# Power-SMPS.net
KiCad netlist of a schematic drawn in Altium Designer
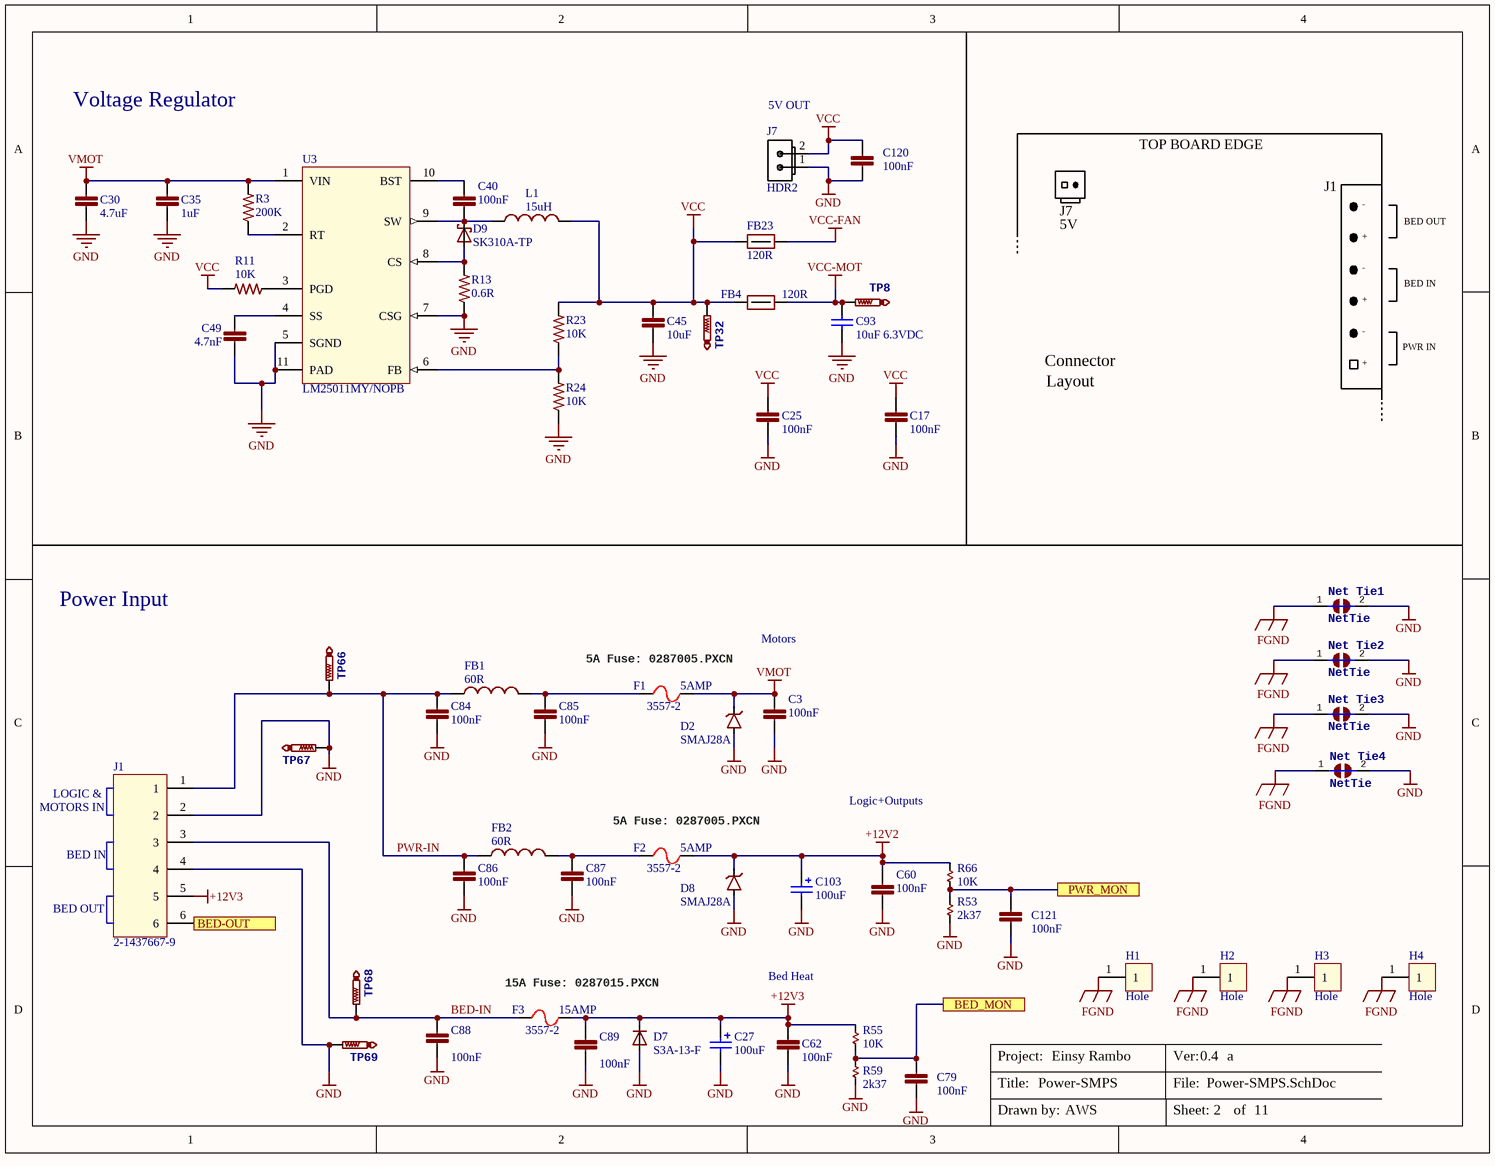
[diagram p0: Power-SMPS.SchDoc]

(export (version "E")
  (design (tool "Eeschema 10.0.6"))
  (components
    (comp (ref "C3")
      (value "100nF")
      (footprint "C0603")
      (description "CAP CER 0603 100nF 50V 10% X7R")
      (fields (field (name "MANUFACTURER") "Kemet") (field (name "TOLERANCE") "+/- 10%"))
      (libsource (lib "3Delight") (part "C0603C104K5RACTU"))
    )
    (comp (ref "C17")
      (value "100nF")
      (footprint "C0402")
      (description "CAP CER 0402 100nF 16V 10% X7R")
      (fields (field (name "MANUFACTURER") "Murata") (field (name "TOLERANCE") "+/- 10%"))
      (libsource (lib "") (part "GRM155R71C104KA88D_2"))
    )
    (comp (ref "C25")
      (value "100nF")
      (footprint "C0603")
      (description "CAP CER 0603 100nF 50V 10% X7R")
      (fields (field (name "MANUFACTURER") "Kemet") (field (name "TOLERANCE") "+/- 10%"))
      (libsource (lib "3Delight") (part "C0603C104K5RACTU"))
    )
    (comp (ref "C27")
      (value "100uF")
      (footprint "CAP-ELEC-063063077")
      (description "CAP ALUM 100UF 35V 20% SMD")
      (fields (field (name "MANUFACTURER") "Nichicon") (field (name "TOLERANCE") "+/- 20%"))
      (libsource (lib "3Delight") (part "UWT1V101MCL1GS"))
    )
    (comp (ref "C30")
      (value "4.7uF")
      (footprint "C1206")
      (description "CAP CER 1206 4.7uF 50V 10% X5R")
      (fields (field (name "MANUFACTURER") "Kemet") (field (name "TOLERANCE") "+/- 10%"))
      (libsource (lib "3Delight") (part "C1206C475K5PACTU"))
    )
    (comp (ref "C35")
      (value "1uF")
      (footprint "C0805")
      (description "CAP CER 0805 1uF 50V 10% X7R")
      (fields (field (name "MANUFACTURER") "Murata") (field (name "TOLERANCE") "+/- 10%"))
      (libsource (lib "3Delight") (part "GRM21BR71H105KA12L"))
    )
    (comp (ref "C40")
      (value "100nF")
      (footprint "C0603")
      (description "CAP CER 0603 100nF 50V 10% X7R")
      (fields (field (name "MANUFACTURER") "Kemet") (field (name "TOLERANCE") "+/- 10%"))
      (libsource (lib "3Delight") (part "C0603C104K5RACTU"))
    )
    (comp (ref "C45")
      (value "10uF")
      (footprint "C0805")
      (description "CAP CER 0805 10uF 10V 10% X5R")
      (fields (field (name "MANUFACTURER") "Kemet") (field (name "TOLERANCE") "+/- 10%"))
      (libsource (lib "3Delight") (part "C0805C106K8PACTU"))
    )
    (comp (ref "C49")
      (value "4.7nF")
      (footprint "C0402")
      (description "CAP CER 0402 4.7nF 25V 10% X7R")
      (fields (field (name "MANUFACTURER") "YAGEO") (field (name "TOLERANCE") "+/- 10%"))
      (libsource (lib "3Delight") (part "CC0402KRX7R8BB472"))
    )
    (comp (ref "C60")
      (value "100nF")
      (footprint "C0603")
      (description "CAP CER 0603 100nF 50V 10% X7R")
      (fields (field (name "MANUFACTURER") "Kemet") (field (name "TOLERANCE") "+/- 10%"))
      (libsource (lib "3Delight") (part "C0603C104K5RACTU"))
    )
    (comp (ref "C62")
      (value "100nF")
      (footprint "C0603")
      (description "CAP CER 0603 100nF 50V 10% X7R")
      (fields (field (name "MANUFACTURER") "Kemet") (field (name "TOLERANCE") "+/- 10%"))
      (libsource (lib "3Delight") (part "C0603C104K5RACTU"))
    )
    (comp (ref "C79")
      (value "100nF")
      (footprint "C0402")
      (description "CAP CER 0402 100nF 16V 10% X7R")
      (fields (field (name "MANUFACTURER") "Murata") (field (name "TOLERANCE") "+/- 10%"))
      (libsource (lib "") (part "GRM155R71C104KA88D_1"))
    )
    (comp (ref "C84")
      (value "100nF")
      (footprint "C0603")
      (description "CAP CER 0603 100nF 50V 10% X7R")
      (fields (field (name "MANUFACTURER") "Kemet") (field (name "TOLERANCE") "+/- 10%"))
      (libsource (lib "3Delight") (part "C0603C104K5RACTU"))
    )
    (comp (ref "C85")
      (value "100nF")
      (footprint "C0603")
      (description "CAP CER 0603 100nF 50V 10% X7R")
      (fields (field (name "MANUFACTURER") "Kemet") (field (name "TOLERANCE") "+/- 10%"))
      (libsource (lib "3Delight") (part "C0603C104K5RACTU"))
    )
    (comp (ref "C86")
      (value "100nF")
      (footprint "C0603")
      (description "CAP CER 0603 100nF 50V 10% X7R")
      (fields (field (name "MANUFACTURER") "Kemet") (field (name "TOLERANCE") "+/- 10%"))
      (libsource (lib "3Delight") (part "C0603C104K5RACTU"))
    )
    (comp (ref "C87")
      (value "100nF")
      (footprint "C0603")
      (description "CAP CER 0603 100nF 50V 10% X7R")
      (fields (field (name "MANUFACTURER") "Kemet") (field (name "TOLERANCE") "+/- 10%"))
      (libsource (lib "3Delight") (part "C0603C104K5RACTU"))
    )
    (comp (ref "C88")
      (value "100nF")
      (footprint "C0603")
      (description "CAP CER 0603 100nF 50V 10% X7R")
      (fields (field (name "MANUFACTURER") "Kemet") (field (name "TOLERANCE") "+/- 10%"))
      (libsource (lib "3Delight") (part "C0603C104K5RACTU"))
    )
    (comp (ref "C89")
      (value "100nF")
      (footprint "C0603")
      (description "CAP CER 0603 100nF 50V 10% X7R")
      (fields (field (name "MANUFACTURER") "Kemet") (field (name "TOLERANCE") "+/- 10%"))
      (libsource (lib "3Delight") (part "C0603C104K5RACTU"))
    )
    (comp (ref "C93")
      (value "10uF 6.3VDC")
      (footprint "C0603")
      (description "CAP CER 10UF 6.3V 10% JB 0603")
      (fields (field (name "TOLERANCE") "+/- 10%") (field (name "MANUFACTURER") "TDK"))
      (libsource (lib "Tigershark3D") (part "C1608JB0J106K080AB"))
    )
    (comp (ref "C103")
      (value "100uF")
      (footprint "CAP-ELEC-063063077")
      (description "CAP ALUM 100UF 35V 20% SMD")
      (fields (field (name "MANUFACTURER") "Nichicon") (field (name "TOLERANCE") "+/- 20%"))
      (libsource (lib "3Delight") (part "UWT1V101MCL1GS"))
    )
    (comp (ref "C120")
      (value "100nF")
      (footprint "C0402")
      (description "CAP CER 0402 100nF 16V 10% X7R")
      (fields (field (name "MANUFACTURER") "Murata") (field (name "TOLERANCE") "+/- 10%"))
      (libsource (lib "3Delight") (part "GRM155R71C104KA88D"))
    )
    (comp (ref "C121")
      (value "100nF")
      (footprint "C0402")
      (description "CAP CER 0402 100nF 16V 10% X7R")
      (fields (field (name "MANUFACTURER") "Murata") (field (name "TOLERANCE") "+/- 10%"))
      (libsource (lib "") (part "GRM155R71C104KA88D_1"))
    )
    (comp (ref "D2")
      (value "SMAJ28A")
      (footprint "SMA-SM")
      (description "TVS DIODE 28VWM 45.4VC SMA")
      (fields (field (name "MANUFACTURER") "Diodes Inc") (field (name "TOLERANCE") "NA"))
      (libsource (lib "Diodes") (part "SMAJ28A"))
    )
    (comp (ref "D7")
      (value "S3A-13-F")
      (footprint "DO-214AB")
      (description "DIODE DO-214AB")
      (fields (field (name "MANUFACTURER") "Diodes Incorporated") (field (name "TOLERANCE") "NA"))
      (libsource (lib "3Delight") (part "S3A-13-F"))
    )
    (comp (ref "D8")
      (value "SMAJ28A")
      (footprint "SMA-SM")
      (description "TVS DIODE 28VWM 45.4VC SMA")
      (fields (field (name "MANUFACTURER") "Diodes Inc") (field (name "TOLERANCE") "NA"))
      (libsource (lib "Diodes") (part "SMAJ28A"))
    )
    (comp (ref "D9")
      (value "SK310A-TP")
      (footprint "SMA-SM")
      (description "DIODE Schottky 3A SMA")
      (fields (field (name "MANUFACTURER") "MCC") (field (name "PART") "SK310A"))
      (libsource (lib "3Delight") (part "SK310A"))
    )
    (comp (ref "F1")
      (value "3557-2")
      (footprint "3557")
      (description "FUSE PTH ATO")
      (fields (field (name "MANUFACTURER") "Keystone") (field (name "PART") "Fuse"))
      (libsource (lib "3Delight") (part "3557-2"))
    )
    (comp (ref "F2")
      (value "3557-2")
      (footprint "3557")
      (description "FUSE PTH ATO")
      (fields (field (name "MANUFACTURER") "Keystone") (field (name "PART") "Fuse"))
      (libsource (lib "3Delight") (part "3557-2"))
    )
    (comp (ref "F3")
      (value "3557-2")
      (footprint "3557")
      (description "FUSE PTH ATO")
      (fields (field (name "MANUFACTURER") "Keystone") (field (name "PART") "Fuse"))
      (libsource (lib "3Delight") (part "3557-2"))
    )
    (comp (ref "FB1")
      (value "60R")
      (footprint "3Delight:L1806")
      (description "FERRITE BEAD 1806 60ohm")
      (fields (field (name "MANUFACTURER") "Murata") (field (name "PART") "60Rf"))
      (libsource (lib "3Delight") (part "BLM41PG600SN1L"))
    )
    (comp (ref "FB2")
      (value "60R")
      (footprint "3Delight:L1806")
      (description "FERRITE BEAD 1806 60ohm")
      (fields (field (name "MANUFACTURER") "Murata") (field (name "PART") "60Rf"))
      (libsource (lib "3Delight") (part "BLM41PG600SN1L"))
    )
    (comp (ref "FB4")
      (value "120R")
      (footprint "FB0603")
      (description "FERRITE BEAD 120 OHM 0603 1LN")
      (fields (field (name "MANUFACTURER") "Samsung") (field (name "PART") "FERRITE 120R 3A 0603"))
      (libsource (lib "3Delight") (part "FERRITE 220R 2.5A 0603"))
    )
    (comp (ref "FB23")
      (value "120R")
      (footprint "FB0603")
      (description "FERRITE BEAD 120 OHM 0603 1LN")
      (fields (field (name "MANUFACTURER") "Samsung") (field (name "PART") "FERRITE 120R 3A 0603"))
      (libsource (lib "Inductors") (part "FERRITE 120R 3A 0603"))
    )
    (comp (ref "H1")
      (value "Hole")
      (footprint "Wave_hole_3x7-singleSided")
      (libsource (lib "3Delight") (part "Hole"))
    )
    (comp (ref "H2")
      (value "Hole")
      (footprint "Wave_hole_3x7-singleSided")
      (libsource (lib "3Delight") (part "Hole"))
    )
    (comp (ref "H3")
      (value "Hole")
      (footprint "Wave_hole_3x7-singleSided")
      (libsource (lib "3Delight") (part "Hole"))
    )
    (comp (ref "H4")
      (value "Hole")
      (footprint "Wave_hole_3x7-singleSided")
      (libsource (lib "3Delight") (part "Hole"))
    )
    (comp (ref "J1")
      (value "2-1437667-9")
      (footprint "CON-Barrier-6-8.26mm")
      (description "CONN BARRIER STRIP 6CIRC 0.325\"")
      (fields (field (name "MANUFACTURER") "TE") (field (name "PART") "6POS"))
      (libsource (lib "3Delight") (part "2-1437667-9"))
    )
    (comp (ref "J7")
      (value "HDR2")
      (footprint "70543-02 PIN-IN-PASTE")
      (description "Connector 2pos")
      (fields (field (name "MANUFACTURER") "Molex") (field (name "PART") "2 Pin Conn"))
      (libsource (lib "Connectors") (part "CONN 2PIN VERT 0.1{dblquote} SHRD LOCKING PIN-IN-PASTE"))
    )
    (comp (ref "L1")
      (value "15uH")
      (footprint "XAL50xx_VLS6045")
      (description "FIXED IND 15UH 2.5A 98 MOHM SMD")
      (fields (field (name "MANUFACTURER") "TDK") (field (name "TOLERANCE") "+/- 20%"))
      (libsource (lib "3Delight") (part "IND 15uH 2.5A 0.075R"))
    )
    (comp (ref "Net Tie1")
      (value "NetTie")
      (footprint "Net Tie")
      (description "Net Tie")
      (fields (field (name "PUBLISHER") "UltiMachine"))
      (libsource (lib "3Delight") (part "NetTie"))
    )
    (comp (ref "Net Tie2")
      (value "NetTie")
      (footprint "Net Tie")
      (description "Net Tie")
      (fields (field (name "PUBLISHER") "UltiMachine"))
      (libsource (lib "3Delight") (part "NetTie"))
    )
    (comp (ref "Net Tie3")
      (value "NetTie")
      (footprint "Net Tie")
      (description "Net Tie")
      (fields (field (name "PUBLISHER") "UltiMachine"))
      (libsource (lib "3Delight") (part "NetTie"))
    )
    (comp (ref "Net Tie4")
      (value "NetTie")
      (footprint "Net Tie")
      (description "Net Tie")
      (fields (field (name "PUBLISHER") "UltiMachine"))
      (libsource (lib "3Delight") (part "NetTie"))
    )
    (comp (ref "R3")
      (value "200K")
      (footprint "R0402")
      (description "RES 0402 200K")
      (fields (field (name "MANUFACTURER") "Vishay Dale") (field (name "TOLERANCE") "+/- 1%"))
      (libsource (lib "3Delight") (part "CRCW0402200KFKED"))
    )
    (comp (ref "R11")
      (value "10K")
      (footprint "R0402")
      (description "RES SMD 10K OHM 1% 1/16W 0402")
      (fields (field (name "MANUFACTURER") "Yageo") (field (name "PART") "10k 1% 0402"))
      (libsource (lib "3Delight") (part "RC0402FR-0710KP"))
    )
    (comp (ref "R13")
      (value "0.6R")
      (footprint "2512R-0.55")
      (description "RES 0.06 OHM 1W 1% 2512 SMD")
      (fields (field (name "MANUFACTURER") "Yageo") (field (name "TOLERANCE") "1%"))
      (libsource (lib "3Delight") (part "RL2512FK-070R06L"))
    )
    (comp (ref "R23")
      (value "10K")
      (footprint "R0402")
      (description "RES SMD 10K OHM 1% 1/16W 0402")
      (fields (field (name "MANUFACTURER") "Yageo") (field (name "PART") "10k 1% 0402"))
      (libsource (lib "3Delight") (part "RC0402FR-0710KP"))
    )
    (comp (ref "R24")
      (value "10K")
      (footprint "R0402")
      (description "RES SMD 10K OHM 1% 1/16W 0402")
      (fields (field (name "MANUFACTURER") "Yageo") (field (name "PART") "10k 1% 0402"))
      (libsource (lib "3Delight") (part "RC0402FR-0710KP"))
    )
    (comp (ref "R53")
      (value "2k37")
      (footprint "R0402")
      (description "RES SMD 2.37K OHM 1% 1/16W 0402")
      (fields (field (name "MANUFACTURER") "Yageo") (field (name "PART") "2.37k"))
      (libsource (lib "3Delight") (part "RC0402FR-072K37L"))
    )
    (comp (ref "R55")
      (value "10K")
      (footprint "R0402")
      (description "RES SMD 10K OHM 1% 1/16W 0402")
      (fields (field (name "MANUFACTURER") "Yageo") (field (name "PART") "10k 1% 0402"))
      (libsource (lib "Resistors") (part "10k 1% 0402"))
    )
    (comp (ref "R59")
      (value "2k37")
      (footprint "R0402")
      (description "RES SMD 2.37K OHM 1% 1/16W 0402")
      (fields (field (name "MANUFACTURER") "Yageo") (field (name "PART") "2.37k"))
      (libsource (lib "3Delight") (part "RC0402FR-072K37L"))
    )
    (comp (ref "R66")
      (value "10K")
      (footprint "R0402")
      (description "RES SMD 10K OHM 1% 1/16W 0402")
      (fields (field (name "MANUFACTURER") "Yageo") (field (name "PART") "10k 1% 0402"))
      (libsource (lib "Resistors") (part "10k 1% 0402"))
    )
    (comp (ref "TP8")
      (value "TestPoint")
      (footprint "TP1-27")
      (description "Test Point")
      (libsource (lib "3Delight") (part "TestPoint"))
    )
    (comp (ref "TP32")
      (value "TestPoint")
      (footprint "TP1-27")
      (description "Test Point")
      (libsource (lib "") (part "TestPoint_3"))
    )
    (comp (ref "TP66")
      (value "TestPoint")
      (footprint "TP1-27")
      (description "Test Point")
      (libsource (lib "") (part "TestPoint_1"))
    )
    (comp (ref "TP67")
      (value "TestPoint")
      (footprint "TP1-27")
      (description "Test Point")
      (libsource (lib "") (part "TestPoint_2"))
    )
    (comp (ref "TP68")
      (value "TestPoint")
      (footprint "TP1-27")
      (description "Test Point")
      (libsource (lib "") (part "TestPoint_1"))
    )
    (comp (ref "TP69")
      (value "TestPoint")
      (footprint "TP1-27")
      (description "Test Point")
      (libsource (lib "3Delight") (part "TestPoint"))
    )
    (comp (ref "U3")
      (value "LM25011MY/NOPB")
      (footprint "VSSOP10_ClosedBotVias")
      (description "REG BUCK")
      (fields
        (field (name "MANUFACTURER") "Texas Instruments")
        (field (name "PART") "IC VREG BUCK ADJ 2A 10MSOP")
      )
      (libsource (lib "ICs-Power") (part "LM25011_ClosedBotVias"))
    )
  )
  (nets
    (net (code "1") (name "+12V2") (class "Default")
      (node (ref "C103") (pin "1") (pinfunction "1_1") (pintype "passive"))
      (node (ref "C60") (pin "1") (pinfunction "1_1") (pintype "passive"))
      (node (ref "D8") (pin "K") (pinfunction "K_K") (pintype "passive"))
      (node (ref "F2") (pin "2") (pinfunction "2_2") (pintype "passive"))
      (node (ref "R66") (pin "2") (pinfunction "2_2") (pintype "passive"))
    )
    (net (code "2") (name "+12V3") (class "Default")
      (node (ref "C27") (pin "1") (pinfunction "1_1") (pintype "passive"))
      (node (ref "C62") (pin "1") (pinfunction "1_1") (pintype "passive"))
      (node (ref "C89") (pin "1") (pinfunction "1_1") (pintype "passive"))
      (node (ref "D7") (pin "C") (pinfunction "C_C") (pintype "passive"))
      (node (ref "F3") (pin "2") (pinfunction "2_2") (pintype "passive"))
      (node (ref "J1") (pin "5") (pinfunction "5_5") (pintype "passive"))
      (node (ref "R55") (pin "2") (pinfunction "2_2") (pintype "passive"))
    )
    (net (code "3") (name "/BED-IN") (class "Default")
      (node (ref "C88") (pin "1") (pinfunction "1_1") (pintype "passive"))
      (node (ref "F3") (pin "1") (pinfunction "1_1") (pintype "passive"))
      (node (ref "J1") (pin "3") (pinfunction "3_3") (pintype "passive"))
      (node (ref "TP68") (pin "TP") (pinfunction "TP_TP") (pintype "passive"))
    )
    (net (code "4") (name "/BED-OUT") (class "Default")
      (node (ref "J1") (pin "6") (pinfunction "6_6") (pintype "passive"))
    )
    (net (code "5") (name "/BED_MON") (class "Default")
      (node (ref "C79") (pin "1") (pinfunction "1_1") (pintype "passive"))
      (node (ref "R55") (pin "1") (pinfunction "1_1") (pintype "passive"))
      (node (ref "R59") (pin "1") (pinfunction "1_1") (pintype "passive"))
    )
    (net (code "6") (name "/PWR-IN") (class "Default")
      (node (ref "C84") (pin "1") (pinfunction "1_1") (pintype "passive"))
      (node (ref "C86") (pin "1") (pinfunction "1_1") (pintype "passive"))
      (node (ref "FB1") (pin "1") (pinfunction "1_1") (pintype "passive"))
      (node (ref "FB2") (pin "1") (pinfunction "1_1") (pintype "passive"))
      (node (ref "J1") (pin "1") (pinfunction "1_1") (pintype "passive"))
      (node (ref "TP66") (pin "TP") (pinfunction "TP_TP") (pintype "passive"))
    )
    (net (code "7") (name "/PWR_MON") (class "Default")
      (node (ref "C121") (pin "1") (pinfunction "1_1") (pintype "passive"))
      (node (ref "R53") (pin "1") (pinfunction "1_1") (pintype "passive"))
      (node (ref "R66") (pin "1") (pinfunction "1_1") (pintype "passive"))
    )
    (net (code "8") (name "FGND") (class "Default")
      (node (ref "H1") (pin "1") (pinfunction "1_1") (pintype "power_in"))
      (node (ref "H2") (pin "1") (pinfunction "1_1") (pintype "power_in"))
      (node (ref "H3") (pin "1") (pinfunction "1_1") (pintype "power_in"))
      (node (ref "H4") (pin "1") (pinfunction "1_1") (pintype "power_in"))
      (node (ref "Net Tie1") (pin "1") (pinfunction "1_1") (pintype "passive"))
      (node (ref "Net Tie2") (pin "1") (pinfunction "1_1") (pintype "passive"))
      (node (ref "Net Tie3") (pin "1") (pinfunction "1_1") (pintype "passive"))
      (node (ref "Net Tie4") (pin "1") (pinfunction "1_1") (pintype "passive"))
    )
    (net (code "9") (name "GND") (class "Default")
      (node (ref "C103") (pin "2") (pinfunction "2_2") (pintype "passive"))
      (node (ref "C120") (pin "1") (pinfunction "1_1") (pintype "passive"))
      (node (ref "C121") (pin "2") (pinfunction "2_2") (pintype "passive"))
      (node (ref "C17") (pin "2") (pinfunction "2_2") (pintype "passive"))
      (node (ref "C25") (pin "2") (pinfunction "2_2") (pintype "passive"))
      (node (ref "C27") (pin "2") (pinfunction "2_2") (pintype "passive"))
      (node (ref "C3") (pin "2") (pinfunction "2_2") (pintype "passive"))
      (node (ref "C30") (pin "2") (pinfunction "2_2") (pintype "passive"))
      (node (ref "C35") (pin "2") (pinfunction "2_2") (pintype "passive"))
      (node (ref "C45") (pin "2") (pinfunction "2_2") (pintype "passive"))
      (node (ref "C49") (pin "2") (pinfunction "2_2") (pintype "passive"))
      (node (ref "C60") (pin "2") (pinfunction "2_2") (pintype "passive"))
      (node (ref "C62") (pin "2") (pinfunction "2_2") (pintype "passive"))
      (node (ref "C79") (pin "2") (pinfunction "2_2") (pintype "passive"))
      (node (ref "C84") (pin "2") (pinfunction "2_2") (pintype "passive"))
      (node (ref "C85") (pin "2") (pinfunction "2_2") (pintype "passive"))
      (node (ref "C86") (pin "2") (pinfunction "2_2") (pintype "passive"))
      (node (ref "C87") (pin "2") (pinfunction "2_2") (pintype "passive"))
      (node (ref "C88") (pin "2") (pinfunction "2_2") (pintype "passive"))
      (node (ref "C89") (pin "2") (pinfunction "2_2") (pintype "passive"))
      (node (ref "C93") (pin "1") (pinfunction "1_1") (pintype "passive"))
      (node (ref "D2") (pin "A") (pinfunction "A_A") (pintype "passive"))
      (node (ref "D7") (pin "A") (pinfunction "A_A") (pintype "passive"))
      (node (ref "D8") (pin "A") (pinfunction "A_A") (pintype "passive"))
      (node (ref "J1") (pin "2") (pinfunction "2_2") (pintype "passive"))
      (node (ref "J1") (pin "4") (pinfunction "4_4") (pintype "passive"))
      (node (ref "J7") (pin "1") (pinfunction "S_1") (pintype "passive"))
      (node (ref "Net Tie1") (pin "2") (pinfunction "2_2") (pintype "passive"))
      (node (ref "Net Tie2") (pin "2") (pinfunction "2_2") (pintype "passive"))
      (node (ref "Net Tie3") (pin "2") (pinfunction "2_2") (pintype "passive"))
      (node (ref "Net Tie4") (pin "2") (pinfunction "2_2") (pintype "passive"))
      (node (ref "R13") (pin "1") (pinfunction "1_1") (pintype "passive"))
      (node (ref "R24") (pin "1") (pinfunction "1_1") (pintype "passive"))
      (node (ref "R53") (pin "2") (pinfunction "2_2") (pintype "passive"))
      (node (ref "R59") (pin "2") (pinfunction "2_2") (pintype "passive"))
      (node (ref "TP67") (pin "TP") (pinfunction "TP_TP") (pintype "passive"))
      (node (ref "TP69") (pin "TP") (pinfunction "TP_TP") (pintype "passive"))
      (node (ref "U3") (pin "11") (pinfunction "PAD_11") (pintype "power_in"))
      (node (ref "U3") (pin "5") (pinfunction "SGND_5") (pintype "power_in"))
      (node (ref "U3") (pin "7") (pinfunction "CSG_7") (pintype "input"))
    )
    (net (code "10") (name "Net-(C85-Pad1)") (class "Default")
      (node (ref "C85") (pin "1") (pinfunction "1_1") (pintype "passive"))
      (node (ref "F1") (pin "1") (pinfunction "1_1") (pintype "passive"))
      (node (ref "FB1") (pin "2") (pinfunction "2_2") (pintype "passive"))
    )
    (net (code "11") (name "Net-(C87-Pad1)") (class "Default")
      (node (ref "C87") (pin "1") (pinfunction "1_1") (pintype "passive"))
      (node (ref "F2") (pin "1") (pinfunction "1_1") (pintype "passive"))
      (node (ref "FB2") (pin "2") (pinfunction "2_2") (pintype "passive"))
    )
    (net (code "12") (name "Net-(U3-BST)") (class "Default")
      (node (ref "C40") (pin "1") (pinfunction "1_1") (pintype "passive"))
      (node (ref "U3") (pin "10") (pinfunction "BST_10") (pintype "power_in"))
    )
    (net (code "13") (name "Net-(U3-CS)") (class "Default")
      (node (ref "D9") (pin "A") (pinfunction "A_A") (pintype "passive"))
      (node (ref "R13") (pin "2") (pinfunction "2_2") (pintype "passive"))
      (node (ref "U3") (pin "8") (pinfunction "CS_8") (pintype "input"))
    )
    (net (code "14") (name "Net-(U3-FB)") (class "Default")
      (node (ref "R23") (pin "1") (pinfunction "1_1") (pintype "passive"))
      (node (ref "R24") (pin "2") (pinfunction "2_2") (pintype "passive"))
      (node (ref "U3") (pin "6") (pinfunction "FB_6") (pintype "input"))
    )
    (net (code "15") (name "Net-(U3-PGD)") (class "Default")
      (node (ref "R11") (pin "1") (pinfunction "1_1") (pintype "passive"))
      (node (ref "U3") (pin "3") (pinfunction "PGD_3") (pintype "power_in"))
    )
    (net (code "16") (name "Net-(U3-RT)") (class "Default")
      (node (ref "R3") (pin "1") (pinfunction "1_1") (pintype "passive"))
      (node (ref "U3") (pin "2") (pinfunction "RT_2") (pintype "power_in"))
    )
    (net (code "17") (name "Net-(U3-SS)") (class "Default")
      (node (ref "C49") (pin "1") (pinfunction "1_1") (pintype "passive"))
      (node (ref "U3") (pin "4") (pinfunction "SS_4") (pintype "power_in"))
    )
    (net (code "18") (name "Net-(U3-SW)") (class "Default")
      (node (ref "C40") (pin "2") (pinfunction "2_2") (pintype "passive"))
      (node (ref "D9") (pin "C") (pinfunction "C_C") (pintype "passive"))
      (node (ref "L1") (pin "1") (pinfunction "1_1") (pintype "passive"))
      (node (ref "U3") (pin "9") (pinfunction "SW_9") (pintype "output"))
    )
    (net (code "19") (name "VCC") (class "Default")
      (node (ref "C120") (pin "2") (pinfunction "2_2") (pintype "passive"))
      (node (ref "C17") (pin "1") (pinfunction "1_1") (pintype "passive"))
      (node (ref "C25") (pin "1") (pinfunction "1_1") (pintype "passive"))
      (node (ref "C45") (pin "1") (pinfunction "1_1") (pintype "passive"))
      (node (ref "FB23") (pin "1") (pinfunction "1_1") (pintype "passive"))
      (node (ref "FB4") (pin "1") (pinfunction "1_1") (pintype "passive"))
      (node (ref "J7") (pin "2") (pinfunction "S_2") (pintype "passive"))
      (node (ref "L1") (pin "2") (pinfunction "2_2") (pintype "passive"))
      (node (ref "R11") (pin "2") (pinfunction "2_2") (pintype "passive"))
      (node (ref "R23") (pin "2") (pinfunction "2_2") (pintype "passive"))
      (node (ref "TP32") (pin "TP") (pinfunction "TP_TP") (pintype "passive"))
    )
    (net (code "20") (name "VCC-FAN") (class "Default")
      (node (ref "FB23") (pin "2") (pinfunction "2_2") (pintype "passive"))
    )
    (net (code "21") (name "VCC-MOT") (class "Default")
      (node (ref "C93") (pin "2") (pinfunction "2_2") (pintype "passive"))
      (node (ref "FB4") (pin "2") (pinfunction "2_2") (pintype "passive"))
      (node (ref "TP8") (pin "TP") (pinfunction "TP_TP") (pintype "passive"))
    )
    (net (code "22") (name "VMOT") (class "Default")
      (node (ref "C3") (pin "1") (pinfunction "1_1") (pintype "passive"))
      (node (ref "C30") (pin "1") (pinfunction "1_1") (pintype "passive"))
      (node (ref "C35") (pin "1") (pinfunction "1_1") (pintype "passive"))
      (node (ref "D2") (pin "K") (pinfunction "K_K") (pintype "passive"))
      (node (ref "F1") (pin "2") (pinfunction "2_2") (pintype "passive"))
      (node (ref "R3") (pin "2") (pinfunction "2_2") (pintype "passive"))
      (node (ref "U3") (pin "1") (pinfunction "VIN_1") (pintype "power_in"))
    )
  )
)
